# schematic.net
KiCad netlist of a schematic drawn in Altium Designer
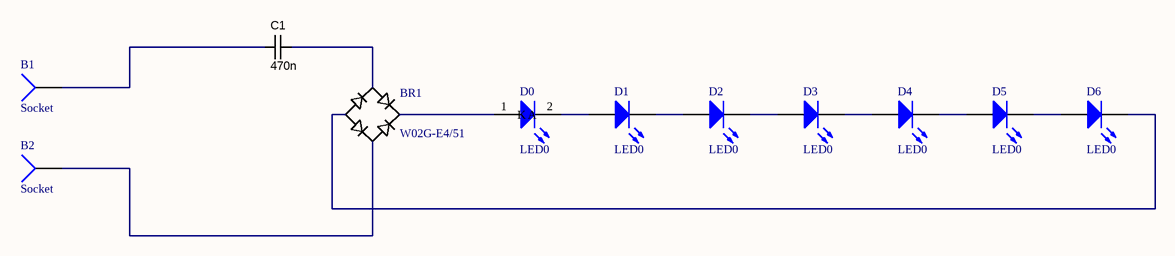
[diagram p0: schematic.SchDoc]

(export (version "E")
  (design (tool "Eeschema 10.0.6"))
  (components
    (comp (ref "B1")
      (value "Socket")
      (footprint "PIN1")
      (fields (field (name "PUBLISHER") "Altium Limited"))
      (libsource (lib "PCB_Nerve-U_01") (part "Socket"))
    )
    (comp (ref "B2")
      (value "Socket")
      (footprint "PIN1")
      (fields (field (name "PUBLISHER") "Altium Limited"))
      (libsource (lib "PCB_Nerve-U_01") (part "Socket"))
    )
    (comp (ref "BR1")
      (value "W02G-E4/51")
      (footprint "DIOB_W02G-E4/51")
      (description "Diode Rectifier Bridge Single 200V 1.5A 4-Pin Case WOG Bulk")
      (fields (field (name "MF") "Vishay"))
      (libsource (lib "W02G-E4_51") (part "W02G-E4/51"))
    )
    (comp (ref "C1")
      (value "470n")
      (footprint "CAPR7.62-6.8x2.5")
      (description "Capacitor THD MK Film 470nF 10% 100V")
      (fields (field (name "TOLERANCE") "±10%"))
      (libsource (lib "PBL - Capacitors") (part "CAPMF_470n_100V_MK"))
    )
    (comp (ref "D0")
      (value "LED0")
      (footprint "LED-0")
      (description "Typical INFRARED GaAs LED")
      (fields (field (name "PUBLISHER") "Altium Limited"))
      (libsource (lib "") (part "LED0_1"))
    )
    (comp (ref "D1")
      (value "LED0")
      (footprint "LED-0")
      (description "Typical INFRARED GaAs LED")
      (fields (field (name "PUBLISHER") "Altium Limited"))
      (libsource (lib "Miscellaneous Devices") (part "LED0"))
    )
    (comp (ref "D2")
      (value "LED0")
      (footprint "LED-0")
      (description "Typical INFRARED GaAs LED")
      (fields (field (name "PUBLISHER") "Altium Limited"))
      (libsource (lib "Miscellaneous Devices") (part "LED0"))
    )
    (comp (ref "D3")
      (value "LED0")
      (footprint "LED-0")
      (description "Typical INFRARED GaAs LED")
      (fields (field (name "PUBLISHER") "Altium Limited"))
      (libsource (lib "Miscellaneous Devices") (part "LED0"))
    )
    (comp (ref "D4")
      (value "LED0")
      (footprint "LED-0")
      (description "Typical INFRARED GaAs LED")
      (fields (field (name "PUBLISHER") "Altium Limited"))
      (libsource (lib "Miscellaneous Devices") (part "LED0"))
    )
    (comp (ref "D5")
      (value "LED0")
      (footprint "LED-0")
      (description "Typical INFRARED GaAs LED")
      (fields (field (name "PUBLISHER") "Altium Limited"))
      (libsource (lib "Miscellaneous Devices") (part "LED0"))
    )
    (comp (ref "D6")
      (value "LED0")
      (footprint "LED-0")
      (description "Typical INFRARED GaAs LED")
      (fields (field (name "PUBLISHER") "Altium Limited"))
      (libsource (lib "Miscellaneous Devices") (part "LED0"))
    )
  )
  (nets
    (net (code "1") (name "Net-(B1-Pad1)") (class "Default")
      (node (ref "B1") (pin "1") (pinfunction "1_1") (pintype "passive"))
      (node (ref "C1") (pin "1") (pintype "passive"))
    )
    (net (code "2") (name "Net-(BR1-+)") (class "Default")
      (node (ref "BR1") (pin "2") (pinfunction "+_2") (pintype "passive"))
      (node (ref "D0") (pin "1") (pinfunction "A_1") (pintype "passive"))
    )
    (net (code "3") (name "Net-(BR1--)") (class "Default")
      (node (ref "BR1") (pin "4") (pinfunction "-_4") (pintype "passive"))
      (node (ref "D6") (pin "2") (pinfunction "K_2") (pintype "passive"))
    )
    (net (code "4") (name "Net-(BR1-AC1)") (class "Default")
      (node (ref "BR1") (pin "1") (pinfunction "AC1_1") (pintype "passive"))
      (node (ref "C1") (pin "2") (pintype "passive"))
    )
    (net (code "5") (name "Net-(BR1-AC2)") (class "Default")
      (node (ref "B2") (pin "1") (pinfunction "1_1") (pintype "passive"))
      (node (ref "BR1") (pin "3") (pinfunction "AC2_3") (pintype "passive"))
    )
    (net (code "6") (name "Net-(D0-K)") (class "Default")
      (node (ref "D0") (pin "2") (pinfunction "K_2") (pintype "passive"))
      (node (ref "D1") (pin "1") (pinfunction "A_1") (pintype "passive"))
    )
    (net (code "7") (name "Net-(D1-K)") (class "Default")
      (node (ref "D1") (pin "2") (pinfunction "K_2") (pintype "passive"))
      (node (ref "D2") (pin "1") (pinfunction "A_1") (pintype "passive"))
    )
    (net (code "8") (name "Net-(D2-K)") (class "Default")
      (node (ref "D2") (pin "2") (pinfunction "K_2") (pintype "passive"))
      (node (ref "D3") (pin "1") (pinfunction "A_1") (pintype "passive"))
    )
    (net (code "9") (name "Net-(D3-K)") (class "Default")
      (node (ref "D3") (pin "2") (pinfunction "K_2") (pintype "passive"))
      (node (ref "D4") (pin "1") (pinfunction "A_1") (pintype "passive"))
    )
    (net (code "10") (name "Net-(D4-K)") (class "Default")
      (node (ref "D4") (pin "2") (pinfunction "K_2") (pintype "passive"))
      (node (ref "D5") (pin "1") (pinfunction "A_1") (pintype "passive"))
    )
    (net (code "11") (name "Net-(D5-K)") (class "Default")
      (node (ref "D5") (pin "2") (pinfunction "K_2") (pintype "passive"))
      (node (ref "D6") (pin "1") (pinfunction "A_1") (pintype "passive"))
    )
  )
)
